# brakelight_V4.net
KiCad netlist of a schematic drawn in EAGLE
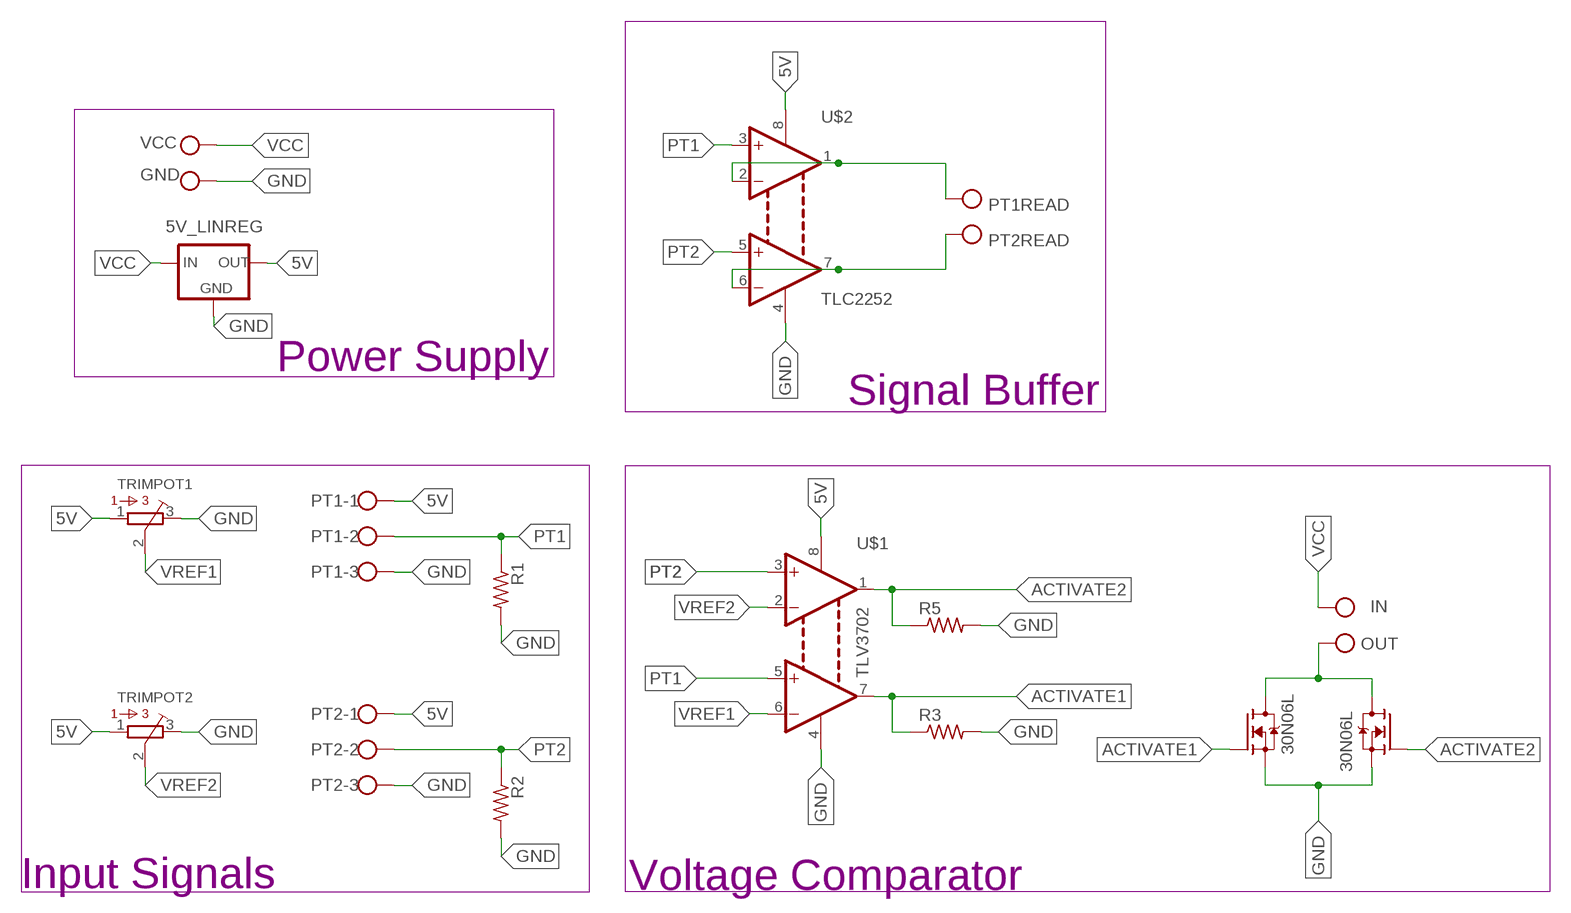
[diagram p0: schematic, sheet 1]

(export (version "E")
  (design (tool "Eeschema 10.0.6"))
  (components
    (comp (ref "5V_LINREG")
      (value "78XXS")
      (footprint "eagle-import:78XXS")
      (libsource (lib "eagle-import") (part "78XXS"))
    )
    (comp (ref "BRAKELIGHT")
      (value "W237-102")
      (footprint "eagle-import:W237-102")
      (fields (field (name "MPN") "237-102"))
      (libsource (lib "eagle-import") (part "W237-102"))
    )
    (comp (ref "INO_READ")
      (value "W237-102")
      (footprint "eagle-import:W237-102")
      (fields (field (name "MPN") "237-102"))
      (libsource (lib "eagle-import") (part "W237-102"))
    )
    (comp (ref "LIPO_CONN")
      (value "W237-102")
      (footprint "eagle-import:W237-102")
      (fields (field (name "MPN") "237-102"))
      (libsource (lib "eagle-import") (part "W237-102"))
    )
    (comp (ref "PT1")
      (value "W237-103")
      (footprint "eagle-import:W237-103")
      (fields (field (name "MPN") "237-103"))
      (libsource (lib "eagle-import") (part "W237-103"))
    )
    (comp (ref "PT2")
      (value "W237-103")
      (footprint "eagle-import:W237-103")
      (fields (field (name "MPN") "237-103"))
      (libsource (lib "eagle-import") (part "W237-103"))
    )
    (comp (ref "Q1")
      (value "30N06L")
      (footprint "eagle-import:TO220V")
      (fields
        (field (name "MF") "ON Semiconductor")
        (field (name "MP") "FQP30N06L")
        (field (name "SPICEPREFIX") "Q")
      )
      (libsource (lib "eagle-import") (part "FQP30N06L"))
    )
    (comp (ref "Q2")
      (value "30N06L")
      (footprint "eagle-import:TO220V")
      (fields
        (field (name "MF") "ON Semiconductor")
        (field (name "MP") "FQP30N06L")
        (field (name "SPICEPREFIX") "Q")
      )
      (libsource (lib "eagle-import") (part "FQP30N06L"))
    )
    (comp (ref "R1")
      (value "R-US_0207/5V")
      (footprint "eagle-import:0207_5V")
      (libsource (lib "eagle-import") (part "R-US_0207/5V"))
    )
    (comp (ref "R2")
      (value "R-US_0207/5V")
      (footprint "eagle-import:0207_5V")
      (libsource (lib "eagle-import") (part "R-US_0207/5V"))
    )
    (comp (ref "R3")
      (value "R-US_0207/5V")
      (footprint "eagle-import:0207_5V")
      (libsource (lib "eagle-import") (part "R-US_0207/5V"))
    )
    (comp (ref "R5")
      (value "R-US_0207/5V")
      (footprint "eagle-import:0207_5V")
      (libsource (lib "eagle-import") (part "R-US_0207/5V"))
    )
    (comp (ref "TRIMPOT1")
      (value "3386-Y")
      (footprint "eagle-import:3386Y")
      (libsource (lib "eagle-import") (part "3386-Y"))
    )
    (comp (ref "TRIMPOT2")
      (value "3386-Y")
      (footprint "eagle-import:3386Y")
      (libsource (lib "eagle-import") (part "3386-Y"))
    )
    (comp (ref "U$1")
      (value "TLV3702")
      (footprint "eagle-import:DIL08")
      (libsource (lib "eagle-import") (part "TLV3702"))
    )
    (comp (ref "U$2")
      (value "TLC2252")
      (footprint "eagle-import:DIL08")
      (libsource (lib "eagle-import") (part "TLC2252"))
    )
  )
  (nets
    (net (code "1") (name "5V") (class "Default")
      (node (ref "5V_LINREG") (pin "OUT") (pinfunction "OUT_OUT") (pintype "passive"))
      (node (ref "PT1") (pin "1") (pinfunction "KL_1") (pintype "passive"))
      (node (ref "PT2") (pin "1") (pinfunction "KL_1") (pintype "passive"))
      (node (ref "TRIMPOT1") (pin "1") (pinfunction "1_1") (pintype "passive"))
      (node (ref "TRIMPOT2") (pin "1") (pinfunction "1_1") (pintype "passive"))
      (node (ref "U$1") (pin "8") (pinfunction "V+_8") (pintype "power_in"))
      (node (ref "U$2") (pin "8") (pinfunction "V+_8") (pintype "power_in"))
    )
    (net (code "2") (name "ACTIVATE1") (class "Default")
      (node (ref "Q2") (pin "1") (pinfunction "G_1") (pintype "passive"))
      (node (ref "R3") (pin "1") (pinfunction "1_1") (pintype "passive"))
      (node (ref "U$1") (pin "7") (pinfunction "2OUT_7") (pintype "output"))
    )
    (net (code "3") (name "ACTIVATE2") (class "Default")
      (node (ref "Q1") (pin "1") (pinfunction "G_1") (pintype "passive"))
      (node (ref "R5") (pin "1") (pinfunction "1_1") (pintype "passive"))
      (node (ref "U$1") (pin "1") (pinfunction "1OUT_1") (pintype "output"))
    )
    (net (code "4") (name "GND") (class "Default")
      (node (ref "5V_LINREG") (pin "GND") (pinfunction "GND_GND") (pintype "input"))
      (node (ref "LIPO_CONN") (pin "2") (pinfunction "KL_2") (pintype "passive"))
      (node (ref "PT1") (pin "3") (pinfunction "KL_3") (pintype "passive"))
      (node (ref "PT2") (pin "3") (pinfunction "KL_3") (pintype "passive"))
      (node (ref "Q1") (pin "3") (pinfunction "S_3") (pintype "passive"))
      (node (ref "Q2") (pin "3") (pinfunction "S_3") (pintype "passive"))
      (node (ref "R1") (pin "2") (pinfunction "2_2") (pintype "passive"))
      (node (ref "R2") (pin "2") (pinfunction "2_2") (pintype "passive"))
      (node (ref "R3") (pin "2") (pinfunction "2_2") (pintype "passive"))
      (node (ref "R5") (pin "2") (pinfunction "2_2") (pintype "passive"))
      (node (ref "TRIMPOT1") (pin "3") (pinfunction "3_3") (pintype "passive"))
      (node (ref "TRIMPOT2") (pin "3") (pinfunction "3_3") (pintype "passive"))
      (node (ref "U$1") (pin "4") (pinfunction "V-_4") (pintype "power_in"))
      (node (ref "U$2") (pin "4") (pinfunction "V-_4") (pintype "power_in"))
    )
    (net (code "5") (name "Net-(BRAKELIGHTB-KL)") (class "Default")
      (node (ref "BRAKELIGHT") (pin "2") (pinfunction "KL_2") (pintype "passive"))
      (node (ref "Q1") (pin "2") (pinfunction "D_2") (pintype "passive"))
      (node (ref "Q2") (pin "2") (pinfunction "D_2") (pintype "passive"))
    )
    (net (code "6") (name "Net-(INO_READA-KL)") (class "Default")
      (node (ref "INO_READ") (pin "1") (pinfunction "KL_1") (pintype "passive"))
      (node (ref "U$2") (pin "1") (pinfunction "1OUT_1") (pintype "output"))
      (node (ref "U$2") (pin "2") (pinfunction "1IN-_2") (pintype "input"))
    )
    (net (code "7") (name "Net-(INO_READB-KL)") (class "Default")
      (node (ref "INO_READ") (pin "2") (pinfunction "KL_2") (pintype "passive"))
      (node (ref "U$2") (pin "6") (pinfunction "2IN-_6") (pintype "input"))
      (node (ref "U$2") (pin "7") (pinfunction "2OUT_7") (pintype "output"))
    )
    (net (code "8") (name "PT1") (class "Default")
      (node (ref "PT1") (pin "2") (pinfunction "KL_2") (pintype "passive"))
      (node (ref "R1") (pin "1") (pinfunction "1_1") (pintype "passive"))
      (node (ref "U$1") (pin "5") (pinfunction "2IN+_5") (pintype "input"))
      (node (ref "U$2") (pin "3") (pinfunction "1IN+_3") (pintype "input"))
    )
    (net (code "9") (name "PT2") (class "Default")
      (node (ref "PT2") (pin "2") (pinfunction "KL_2") (pintype "passive"))
      (node (ref "R2") (pin "1") (pinfunction "1_1") (pintype "passive"))
      (node (ref "U$1") (pin "3") (pinfunction "1IN+_3") (pintype "input"))
      (node (ref "U$2") (pin "5") (pinfunction "2IN+_5") (pintype "input"))
    )
    (net (code "10") (name "VCC") (class "Default")
      (node (ref "5V_LINREG") (pin "IN") (pinfunction "IN_IN") (pintype "input"))
      (node (ref "BRAKELIGHT") (pin "1") (pinfunction "KL_1") (pintype "passive"))
      (node (ref "LIPO_CONN") (pin "1") (pinfunction "KL_1") (pintype "passive"))
    )
    (net (code "11") (name "VREF1") (class "Default")
      (node (ref "TRIMPOT1") (pin "2") (pinfunction "2_2") (pintype "passive"))
      (node (ref "U$1") (pin "6") (pinfunction "2IN-_6") (pintype "input"))
    )
    (net (code "12") (name "VREF2") (class "Default")
      (node (ref "TRIMPOT2") (pin "2") (pinfunction "2_2") (pintype "passive"))
      (node (ref "U$1") (pin "2") (pinfunction "1IN-_2") (pintype "input"))
    )
  )
)
